# board.net
KiCad netlist of a schematic drawn in EAGLE
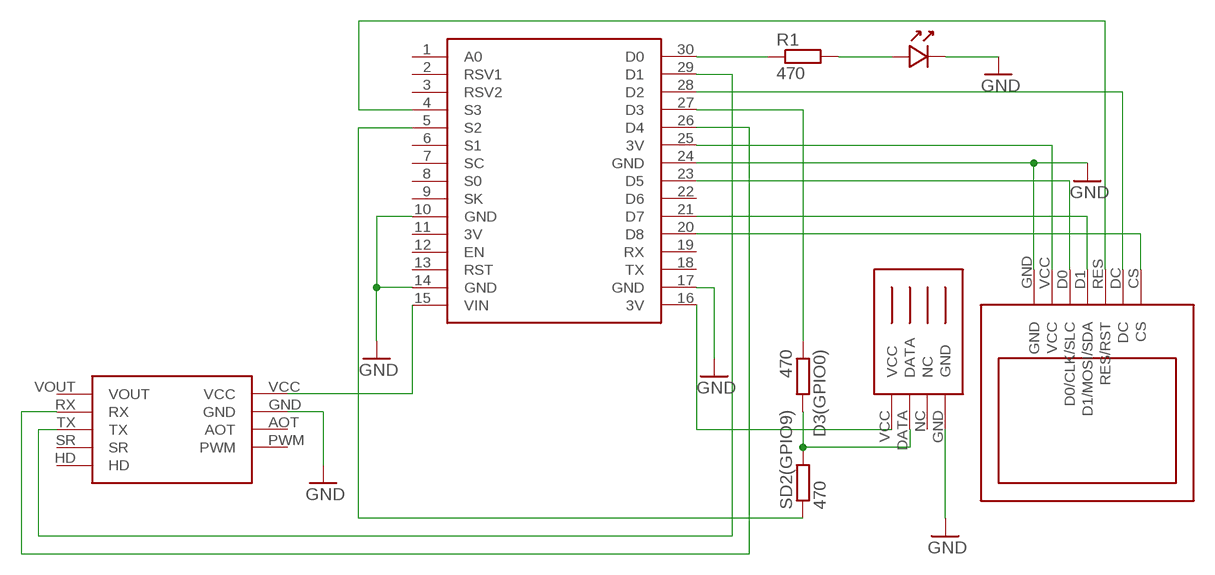
[diagram p0: schematic, sheet 1]

(export (version "E")
  (design (tool "Eeschema 10.0.6"))
  (components
    (comp (ref "D3(GPIO0)")
      (value "470")
      (footprint "eagle-import:M1206")
      (libsource (lib "eagle-import") (part "R-EU_M1206"))
    )
    (comp (ref "R1")
      (value "470")
      (footprint "eagle-import:M1206")
      (libsource (lib "eagle-import") (part "R-EU_M1206"))
    )
    (comp (ref "SD2(GPIO9)")
      (value "470")
      (footprint "eagle-import:M1206")
      (libsource (lib "eagle-import") (part "R-EU_M1206"))
    )
    (comp (ref "U$1")
      (value "NODEMCUV3")
      (footprint "eagle-import:NODEMCU_V3")
      (libsource (lib "eagle-import") (part "NODEMCUV3"))
    )
    (comp (ref "U$2")
      (value "DHT11DEF")
      (footprint "eagle-import:DHT11")
      (libsource (lib "eagle-import") (part "DHT11DEF"))
    )
    (comp (ref "U$3")
      (value "MH_Z19BDEF")
      (footprint "eagle-import:MH_Z19B")
      (libsource (lib "eagle-import") (part "MH_Z19BDEF"))
    )
    (comp (ref "U$4")
      (value "OLED_1.3_V2.0DEF")
      (footprint "eagle-import:OLED_1.3_V2.0")
      (libsource (lib "eagle-import") (part "OLED_1.3_V2.0DEF"))
    )
    (comp (ref "U$6")
      (value "LED_3MLED3M_3D")
      (footprint "eagle-import:LEDRD254W60D300H500B")
      (libsource (lib "eagle-import") (part "LED_3MLED3M_3D"))
    )
  )
  (nets
    (net (code "1") (name "/3V") (class "Default")
      (node (ref "U$1") (pin "11") (pinfunction "3V_11") (pintype "power_in"))
    )
    (net (code "2") (name "GND") (class "Default")
      (node (ref "U$1") (pin "10") (pinfunction "GND_10") (pintype "power_in"))
      (node (ref "U$1") (pin "14") (pinfunction "GND_14") (pintype "power_in"))
      (node (ref "U$1") (pin "17") (pinfunction "GND_17") (pintype "power_in"))
      (node (ref "U$1") (pin "24") (pinfunction "GND_24") (pintype "power_in"))
      (node (ref "U$2") (pin "GND") (pinfunction "GND_GND") (pintype "power_in"))
      (node (ref "U$3") (pin "GND") (pinfunction "GND_GND") (pintype "power_in"))
      (node (ref "U$4") (pin "GND") (pinfunction "GND_GND") (pintype "power_in"))
      (node (ref "U$6") (pin "2") (pinfunction "K_2") (pintype "bidirectional"))
    )
    (net (code "3") (name "Net-(D3(GPIO0)-Pad2)") (class "Default")
      (node (ref "D3(GPIO0)") (pin "2") (pinfunction "2_2") (pintype "passive"))
      (node (ref "SD2(GPIO9)") (pin "2") (pinfunction "2_2") (pintype "passive"))
      (node (ref "U$2") (pin "DATA") (pinfunction "DATA_DATA") (pintype "bidirectional"))
    )
    (net (code "4") (name "Net-(U$1-3V-Pad16)") (class "Default")
      (node (ref "U$1") (pin "16") (pinfunction "3V_16") (pintype "power_in"))
      (node (ref "U$2") (pin "VCC") (pinfunction "VCC_VCC") (pintype "power_in"))
    )
    (net (code "5") (name "Net-(U$1-3V-Pad25)") (class "Default")
      (node (ref "U$1") (pin "25") (pinfunction "3V_25") (pintype "power_in"))
      (node (ref "U$4") (pin "VCC") (pinfunction "VCC_VCC") (pintype "power_in"))
    )
    (net (code "6") (name "Net-(U$1-D0)") (class "Default")
      (node (ref "R1") (pin "1") (pinfunction "1_1") (pintype "passive"))
      (node (ref "U$1") (pin "30") (pinfunction "D0_30") (pintype "bidirectional"))
    )
    (net (code "7") (name "Net-(U$1-D1)") (class "Default")
      (node (ref "U$1") (pin "29") (pinfunction "D1_29") (pintype "bidirectional"))
      (node (ref "U$3") (pin "TX") (pinfunction "TX_TX") (pintype "bidirectional"))
    )
    (net (code "8") (name "Net-(U$1-D2)") (class "Default")
      (node (ref "U$1") (pin "28") (pinfunction "D2_28") (pintype "bidirectional"))
      (node (ref "U$4") (pin "DC") (pinfunction "DC_DC") (pintype "bidirectional"))
    )
    (net (code "9") (name "Net-(U$1-D3)") (class "Default")
      (node (ref "D3(GPIO0)") (pin "1") (pinfunction "1_1") (pintype "passive"))
      (node (ref "U$1") (pin "27") (pinfunction "D3_27") (pintype "bidirectional"))
    )
    (net (code "10") (name "Net-(U$1-D4)") (class "Default")
      (node (ref "U$1") (pin "26") (pinfunction "D4_26") (pintype "bidirectional"))
      (node (ref "U$3") (pin "RX") (pinfunction "RX_RX") (pintype "bidirectional"))
    )
    (net (code "11") (name "Net-(U$1-D5)") (class "Default")
      (node (ref "U$1") (pin "23") (pinfunction "D5_23") (pintype "bidirectional"))
      (node (ref "U$4") (pin "D0") (pinfunction "D0/CLK/SLC_D0") (pintype "bidirectional"))
    )
    (net (code "12") (name "Net-(U$1-D7)") (class "Default")
      (node (ref "U$1") (pin "21") (pinfunction "D7_21") (pintype "bidirectional"))
      (node (ref "U$4") (pin "D1") (pinfunction "D1/MOSI/SDA_D1") (pintype "bidirectional"))
    )
    (net (code "13") (name "Net-(U$1-D8)") (class "Default")
      (node (ref "U$1") (pin "20") (pinfunction "D8_20") (pintype "bidirectional"))
      (node (ref "U$4") (pin "CS") (pinfunction "CS_CS") (pintype "bidirectional"))
    )
    (net (code "14") (name "Net-(U$1-S2)") (class "Default")
      (node (ref "SD2(GPIO9)") (pin "1") (pinfunction "1_1") (pintype "passive"))
      (node (ref "U$1") (pin "5") (pinfunction "S2_5") (pintype "bidirectional"))
    )
    (net (code "15") (name "Net-(U$1-S3)") (class "Default")
      (node (ref "U$1") (pin "4") (pinfunction "S3_4") (pintype "bidirectional"))
      (node (ref "U$4") (pin "RES") (pinfunction "RES/RST_RES") (pintype "bidirectional"))
    )
    (net (code "16") (name "Net-(U$1-VIN)") (class "Default")
      (node (ref "U$1") (pin "15") (pinfunction "VIN_15") (pintype "power_in"))
      (node (ref "U$3") (pin "VCC") (pinfunction "VCC_VCC") (pintype "power_in"))
    )
    (net (code "17") (name "Net-(U$6-A)") (class "Default")
      (node (ref "R1") (pin "2") (pinfunction "2_2") (pintype "passive"))
      (node (ref "U$6") (pin "1") (pinfunction "A_1") (pintype "bidirectional"))
    )
    (net (code "18") (name "unconnected-(U$1-A0-Pad1)") (class "Default")
      (node (ref "U$1") (pin "1") (pinfunction "A0_1") (pintype "bidirectional"))
    )
    (net (code "19") (name "unconnected-(U$1-D6-Pad22)") (class "Default")
      (node (ref "U$1") (pin "22") (pinfunction "D6_22") (pintype "bidirectional"))
    )
    (net (code "20") (name "unconnected-(U$1-EN-Pad12)") (class "Default")
      (node (ref "U$1") (pin "12") (pinfunction "EN_12") (pintype "bidirectional"))
    )
    (net (code "21") (name "unconnected-(U$1-RST-Pad13)") (class "Default")
      (node (ref "U$1") (pin "13") (pinfunction "RST_13") (pintype "bidirectional"))
    )
    (net (code "22") (name "unconnected-(U$1-RSV1-Pad2)") (class "Default")
      (node (ref "U$1") (pin "2") (pinfunction "RSV1_2") (pintype "no_connect"))
    )
    (net (code "23") (name "unconnected-(U$1-RSV2-Pad3)") (class "Default")
      (node (ref "U$1") (pin "3") (pinfunction "RSV2_3") (pintype "no_connect"))
    )
    (net (code "24") (name "unconnected-(U$1-RX-Pad19)") (class "Default")
      (node (ref "U$1") (pin "19") (pinfunction "RX_19") (pintype "bidirectional"))
    )
    (net (code "25") (name "unconnected-(U$1-S0-Pad8)") (class "Default")
      (node (ref "U$1") (pin "8") (pinfunction "S0_8") (pintype "bidirectional"))
    )
    (net (code "26") (name "unconnected-(U$1-S1-Pad6)") (class "Default")
      (node (ref "U$1") (pin "6") (pinfunction "S1_6") (pintype "bidirectional"))
    )
    (net (code "27") (name "unconnected-(U$1-SC-Pad7)") (class "Default")
      (node (ref "U$1") (pin "7") (pinfunction "SC_7") (pintype "bidirectional"))
    )
    (net (code "28") (name "unconnected-(U$1-SK-Pad9)") (class "Default")
      (node (ref "U$1") (pin "9") (pinfunction "SK_9") (pintype "bidirectional"))
    )
    (net (code "29") (name "unconnected-(U$1-TX-Pad18)") (class "Default")
      (node (ref "U$1") (pin "18") (pinfunction "TX_18") (pintype "bidirectional"))
    )
    (net (code "30") (name "unconnected-(U$2-PadNC)") (class "Default")
      (node (ref "U$2") (pin "NC") (pinfunction "NC_NC") (pintype "no_connect"))
    )
    (net (code "31") (name "unconnected-(U$3-PadAOT)") (class "Default")
      (node (ref "U$3") (pin "AOT") (pinfunction "AOT_AOT") (pintype "no_connect"))
    )
    (net (code "32") (name "unconnected-(U$3-PadHD)") (class "Default")
      (node (ref "U$3") (pin "HD") (pinfunction "HD_HD") (pintype "no_connect"))
    )
    (net (code "33") (name "unconnected-(U$3-PadPWM)") (class "Default")
      (node (ref "U$3") (pin "PWM") (pinfunction "PWM_PWM") (pintype "output"))
    )
    (net (code "34") (name "unconnected-(U$3-PadSR)") (class "Default")
      (node (ref "U$3") (pin "SR") (pinfunction "SR_SR") (pintype "no_connect"))
    )
    (net (code "35") (name "unconnected-(U$3-PadVOUT)") (class "Default")
      (node (ref "U$3") (pin "VOUT") (pinfunction "VOUT_VOUT") (pintype "no_connect"))
    )
  )
)
